# MAXIM-ADC2.net
KiCad netlist of a schematic drawn in Altium Designer
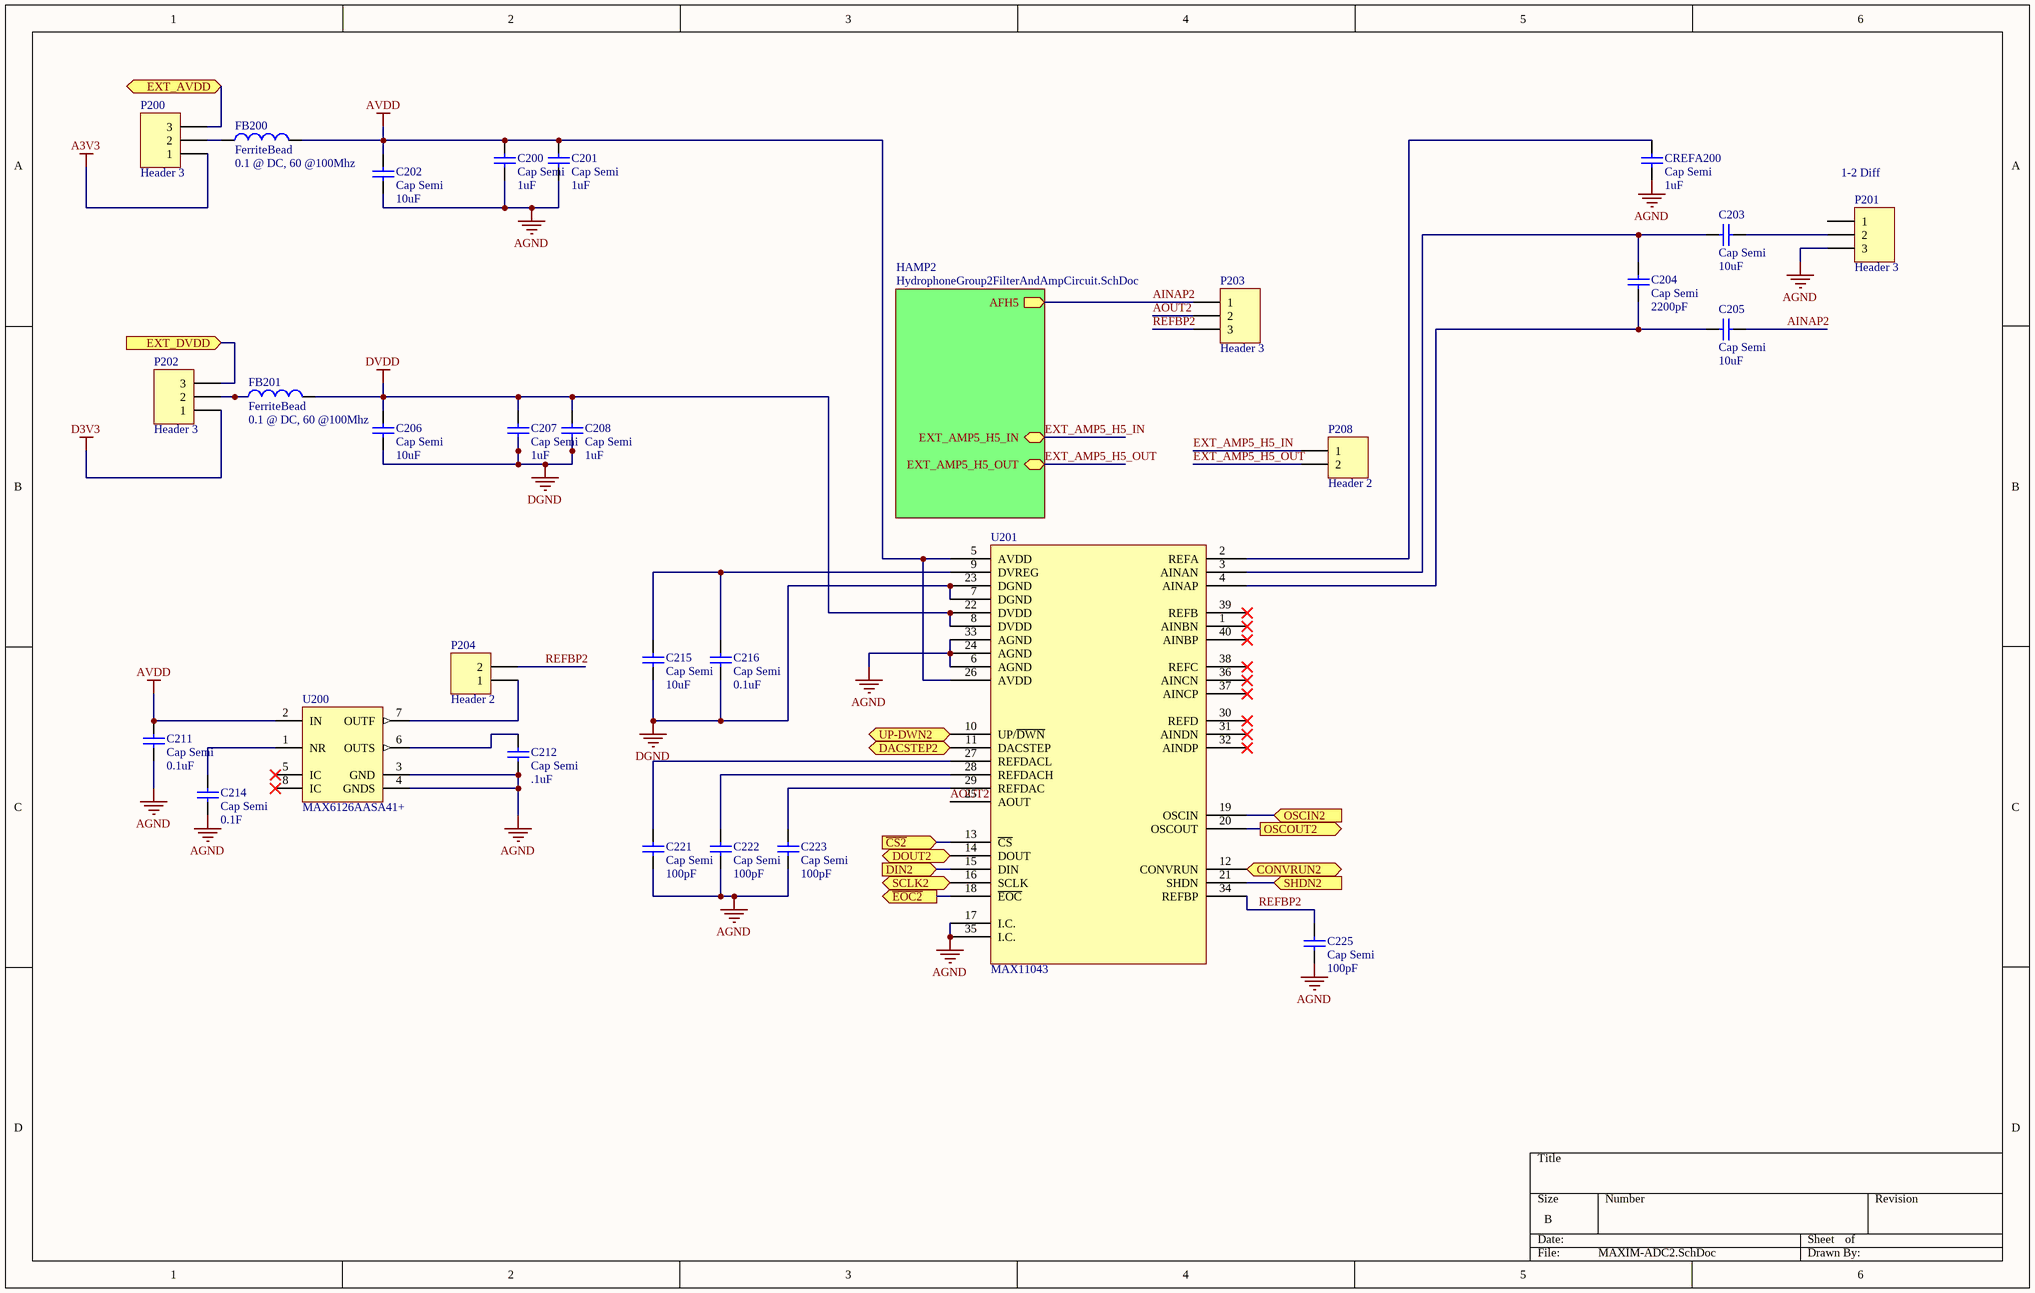
[diagram p0: MAXIM-ADC2.SchDoc]

(export (version "E")
  (design (tool "Eeschema 10.0.6"))
  (components
    (comp (ref "C200")
      (value "Cap Semi")
      (footprint "1608[0603]")
      (description "Capacitor (Semiconductor SIM Model)")
      (fields (field (name "ALTIUM_VALUE") "1uF") (field (name "PUBLISHER") "Altium Limited"))
      (libsource (lib "Miscellaneous Devices") (part "Cap Semi"))
    )
    (comp (ref "C201")
      (value "Cap Semi")
      (footprint "1608[0603]")
      (description "Capacitor (Semiconductor SIM Model)")
      (fields (field (name "ALTIUM_VALUE") "1uF") (field (name "PUBLISHER") "Altium Limited"))
      (libsource (lib "Miscellaneous Devices") (part "Cap Semi"))
    )
    (comp (ref "C202")
      (value "Cap Semi")
      (footprint "1608[0603]")
      (description "Capacitor (Semiconductor SIM Model)")
      (fields (field (name "ALTIUM_VALUE") "10uF") (field (name "PUBLISHER") "Altium Limited"))
      (libsource (lib "Miscellaneous Devices") (part "Cap Semi"))
    )
    (comp (ref "C203")
      (value "Cap Semi")
      (footprint "1608[0603]")
      (description "Capacitor (Semiconductor SIM Model)")
      (fields (field (name "ALTIUM_VALUE") "10uF") (field (name "PUBLISHER") "Altium Limited"))
      (libsource (lib "Miscellaneous Devices") (part "Cap Semi"))
    )
    (comp (ref "C204")
      (value "Cap Semi")
      (footprint "1608[0603]")
      (description "Capacitor (Semiconductor SIM Model)")
      (fields (field (name "ALTIUM_VALUE") "2200pF") (field (name "PUBLISHER") "Altium Limited"))
      (libsource (lib "Miscellaneous Devices") (part "Cap Semi"))
    )
    (comp (ref "C205")
      (value "Cap Semi")
      (footprint "1608[0603]")
      (description "Capacitor (Semiconductor SIM Model)")
      (fields (field (name "ALTIUM_VALUE") "10uF") (field (name "PUBLISHER") "Altium Limited"))
      (libsource (lib "Miscellaneous Devices") (part "Cap Semi"))
    )
    (comp (ref "C206")
      (value "Cap Semi")
      (footprint "1608[0603]")
      (description "Capacitor (Semiconductor SIM Model)")
      (fields (field (name "ALTIUM_VALUE") "10uF") (field (name "PUBLISHER") "Altium Limited"))
      (libsource (lib "Miscellaneous Devices") (part "Cap Semi"))
    )
    (comp (ref "C207")
      (value "Cap Semi")
      (footprint "1608[0603]")
      (description "Capacitor (Semiconductor SIM Model)")
      (fields (field (name "ALTIUM_VALUE") "1uF") (field (name "PUBLISHER") "Altium Limited"))
      (libsource (lib "Miscellaneous Devices") (part "Cap Semi"))
    )
    (comp (ref "C208")
      (value "Cap Semi")
      (footprint "1608[0603]")
      (description "Capacitor (Semiconductor SIM Model)")
      (fields (field (name "ALTIUM_VALUE") "1uF") (field (name "PUBLISHER") "Altium Limited"))
      (libsource (lib "Miscellaneous Devices") (part "Cap Semi"))
    )
    (comp (ref "C211")
      (value "Cap Semi")
      (footprint "1608[0603]")
      (description "Capacitor (Semiconductor SIM Model)")
      (fields (field (name "ALTIUM_VALUE") "0.1uF") (field (name "PUBLISHER") "Altium Limited"))
      (libsource (lib "Miscellaneous Devices") (part "Cap Semi"))
    )
    (comp (ref "C212")
      (value "Cap Semi")
      (footprint "1608[0603]")
      (description "Capacitor (Semiconductor SIM Model)")
      (fields (field (name "ALTIUM_VALUE") ".1uF") (field (name "PUBLISHER") "Altium Limited"))
      (libsource (lib "Miscellaneous Devices") (part "Cap Semi"))
    )
    (comp (ref "C214")
      (value "Cap Semi")
      (footprint "1608[0603]")
      (description "Capacitor (Semiconductor SIM Model)")
      (fields (field (name "ALTIUM_VALUE") "0.1F") (field (name "PUBLISHER") "Altium Limited"))
      (libsource (lib "Miscellaneous Devices") (part "Cap Semi"))
    )
    (comp (ref "C215")
      (value "Cap Semi")
      (footprint "1608[0603]")
      (description "Capacitor (Semiconductor SIM Model)")
      (fields (field (name "ALTIUM_VALUE") "10uF") (field (name "PUBLISHER") "Altium Limited"))
      (libsource (lib "Miscellaneous Devices") (part "Cap Semi"))
    )
    (comp (ref "C216")
      (value "Cap Semi")
      (footprint "1608[0603]")
      (description "Capacitor (Semiconductor SIM Model)")
      (fields (field (name "ALTIUM_VALUE") "0.1uF") (field (name "PUBLISHER") "Altium Limited"))
      (libsource (lib "Miscellaneous Devices") (part "Cap Semi"))
    )
    (comp (ref "C221")
      (value "Cap Semi")
      (footprint "1608[0603]")
      (description "Capacitor (Semiconductor SIM Model)")
      (fields (field (name "ALTIUM_VALUE") "100pF") (field (name "PUBLISHER") "Altium Limited"))
      (libsource (lib "Miscellaneous Devices") (part "Cap Semi"))
    )
    (comp (ref "C222")
      (value "Cap Semi")
      (footprint "1608[0603]")
      (description "Capacitor (Semiconductor SIM Model)")
      (fields (field (name "ALTIUM_VALUE") "100pF") (field (name "PUBLISHER") "Altium Limited"))
      (libsource (lib "Miscellaneous Devices") (part "Cap Semi"))
    )
    (comp (ref "C223")
      (value "Cap Semi")
      (footprint "1608[0603]")
      (description "Capacitor (Semiconductor SIM Model)")
      (fields (field (name "ALTIUM_VALUE") "100pF") (field (name "PUBLISHER") "Altium Limited"))
      (libsource (lib "Miscellaneous Devices") (part "Cap Semi"))
    )
    (comp (ref "C225")
      (value "Cap Semi")
      (footprint "1608[0603]")
      (description "Capacitor (Semiconductor SIM Model)")
      (fields (field (name "ALTIUM_VALUE") "100pF") (field (name "PUBLISHER") "Altium Limited"))
      (libsource (lib "Miscellaneous Devices") (part "Cap Semi"))
    )
    (comp (ref "CREFA200")
      (value "Cap Semi")
      (footprint "1608[0603]")
      (description "Capacitor (Semiconductor SIM Model)")
      (fields (field (name "ALTIUM_VALUE") "1uF") (field (name "PUBLISHER") "Altium Limited"))
      (libsource (lib "Miscellaneous Devices") (part "Cap Semi"))
    )
    (comp (ref "FB200")
      (value "FerriteBead")
      (footprint "0603")
      (description "Inductor")
      (fields
        (field (name "ALTIUM_VALUE") "0.1 @ DC, 60 @100Mhz")
        (field (name "PUBLISHER") "Altium Limited")
      )
      (libsource (lib "Miscellaneous Devices") (part "Inductor"))
    )
    (comp (ref "FB201")
      (value "FerriteBead")
      (footprint "0603")
      (description "Inductor")
      (fields
        (field (name "ALTIUM_VALUE") "0.1 @ DC, 60 @100Mhz")
        (field (name "PUBLISHER") "Altium Limited")
      )
      (libsource (lib "Miscellaneous Devices") (part "Inductor"))
    )
    (comp (ref "P200")
      (value "Header 3")
      (footprint "HDR1X3")
      (description "Header, 3-Pin")
      (fields (field (name "PUBLISHER") "Altium Limited"))
      (libsource (lib "Miscellaneous Connectors") (part "Header 3"))
    )
    (comp (ref "P201")
      (value "Header 3")
      (footprint "HDR1X3")
      (description "Header, 3-Pin")
      (fields (field (name "PUBLISHER") "Altium Limited"))
      (libsource (lib "") (part "Header 3_1"))
    )
    (comp (ref "P202")
      (value "Header 3")
      (footprint "HDR1X3")
      (description "Header, 3-Pin")
      (fields (field (name "PUBLISHER") "Altium Limited"))
      (libsource (lib "Miscellaneous Connectors") (part "Header 3"))
    )
    (comp (ref "P203")
      (value "Header 3")
      (footprint "HDR1X3")
      (description "Header, 3-Pin")
      (fields (field (name "PUBLISHER") "Altium Limited"))
      (libsource (lib "") (part "Header 3_1"))
    )
    (comp (ref "P204")
      (value "Header 2")
      (footprint "HDR1X2")
      (description "Header, 2-Pin")
      (fields (field (name "PUBLISHER") "Altium Limited"))
      (libsource (lib "") (part "Header 2_1"))
    )
    (comp (ref "P208")
      (value "Header 2")
      (footprint "HDR1X2")
      (description "Header, 2-Pin")
      (fields (field (name "PUBLISHER") "Altium Limited"))
      (libsource (lib "Miscellaneous Connectors") (part "Header 2"))
    )
    (comp (ref "U200")
      (value "MAX6126AASA41+")
      (footprint "MAXM-S8+4_M")
      (fields (field (name "MANUFACTURER") "Maxim"))
      (libsource (lib "altium-import") (part "root_0_CMP-0977-00016-1_"))
    )
    (comp (ref "U201")
      (value "MAX11043")
      (footprint "QFN50P600X600X80_HS-41N")
      (libsource (lib "Max11043") (part "MAX11043"))
    )
  )
  (nets
    (net (code "1") (name "/AINAP2") (class "Default")
      (node (ref "C205") (pin "1") (pinfunction "1_1") (pintype "passive"))
      (node (ref "P203") (pin "1") (pinfunction "1_1") (pintype "passive"))
    )
    (net (code "2") (name "/AOUT2") (class "Default")
      (node (ref "P203") (pin "2") (pinfunction "2_2") (pintype "passive"))
      (node (ref "U201") (pin "25") (pinfunction "AOUT_25") (pintype "passive"))
    )
    (net (code "3") (name "/CONVRUN2") (class "Default")
      (node (ref "U201") (pin "12") (pinfunction "CONVRUN_12") (pintype "passive"))
    )
    (net (code "4") (name "/DACSTEP2") (class "Default")
      (node (ref "U201") (pin "11") (pinfunction "DACSTEP_11") (pintype "passive"))
    )
    (net (code "5") (name "/DIN2") (class "Default")
      (node (ref "U201") (pin "15") (pinfunction "DIN_15") (pintype "passive"))
    )
    (net (code "6") (name "/DOUT2") (class "Default")
      (node (ref "U201") (pin "14") (pinfunction "DOUT_14") (pintype "passive"))
    )
    (net (code "7") (name "/EXT_AMP5_H5_IN") (class "Default")
      (node (ref "P208") (pin "1") (pinfunction "1_1") (pintype "passive"))
    )
    (net (code "8") (name "/EXT_AMP5_H5_OUT") (class "Default")
      (node (ref "P208") (pin "2") (pinfunction "2_2") (pintype "passive"))
    )
    (net (code "9") (name "/EXT_AVDD") (class "Default")
      (node (ref "P200") (pin "3") (pinfunction "3_3") (pintype "passive"))
    )
    (net (code "10") (name "/EXT_DVDD") (class "Default")
      (node (ref "P202") (pin "3") (pinfunction "3_3") (pintype "passive"))
    )
    (net (code "11") (name "/OSCIN2") (class "Default")
      (node (ref "U201") (pin "19") (pinfunction "OSCIN_19") (pintype "passive"))
    )
    (net (code "12") (name "/OSCOUT2") (class "Default")
      (node (ref "U201") (pin "20") (pinfunction "OSCOUT_20") (pintype "passive"))
    )
    (net (code "13") (name "/REFBP2") (class "Default")
      (node (ref "C225") (pin "1") (pinfunction "1_1") (pintype "passive"))
      (node (ref "P203") (pin "3") (pinfunction "3_3") (pintype "passive"))
      (node (ref "P204") (pin "2") (pinfunction "2_2") (pintype "passive"))
      (node (ref "U201") (pin "34") (pinfunction "REFBP_34") (pintype "passive"))
    )
    (net (code "14") (name "/SCLK2") (class "Default")
      (node (ref "U201") (pin "16") (pinfunction "SCLK_16") (pintype "passive"))
    )
    (net (code "15") (name "/SHDN2") (class "Default")
      (node (ref "U201") (pin "21") (pinfunction "SHDN_21") (pintype "passive"))
    )
    (net (code "16") (name "/UP-DWN2") (class "Default")
      (node (ref "U201") (pin "10") (pinfunction "UP/~{DWN}_10") (pintype "passive"))
    )
    (net (code "17") (name "/~{CS2}") (class "Default")
      (node (ref "U201") (pin "13") (pinfunction "~{CS}_13") (pintype "passive"))
    )
    (net (code "18") (name "/~{EOC2}") (class "Default")
      (node (ref "U201") (pin "18") (pinfunction "~{EOC}_18") (pintype "passive"))
    )
    (net (code "19") (name "A3V3") (class "Default")
      (node (ref "P200") (pin "1") (pinfunction "1_1") (pintype "passive"))
    )
    (net (code "20") (name "AGND") (class "Default")
      (node (ref "C200") (pin "2") (pinfunction "2_2") (pintype "passive"))
      (node (ref "C201") (pin "2") (pinfunction "2_2") (pintype "passive"))
      (node (ref "C202") (pin "2") (pinfunction "2_2") (pintype "passive"))
      (node (ref "C211") (pin "2") (pinfunction "2_2") (pintype "passive"))
      (node (ref "C212") (pin "2") (pinfunction "2_2") (pintype "passive"))
      (node (ref "C214") (pin "2") (pinfunction "2_2") (pintype "passive"))
      (node (ref "C221") (pin "1") (pinfunction "1_1") (pintype "passive"))
      (node (ref "C222") (pin "2") (pinfunction "2_2") (pintype "passive"))
      (node (ref "C223") (pin "1") (pinfunction "1_1") (pintype "passive"))
      (node (ref "C225") (pin "2") (pinfunction "2_2") (pintype "passive"))
      (node (ref "CREFA200") (pin "1") (pinfunction "1_1") (pintype "passive"))
      (node (ref "P201") (pin "3") (pinfunction "3_3") (pintype "passive"))
      (node (ref "U200") (pin "3") (pinfunction "GND_3") (pintype "power_in"))
      (node (ref "U200") (pin "4") (pinfunction "GNDS_4") (pintype "power_in"))
      (node (ref "U201") (pin "17") (pinfunction "I.C._17") (pintype "passive"))
      (node (ref "U201") (pin "24") (pinfunction "AGND_24") (pintype "passive"))
      (node (ref "U201") (pin "33") (pinfunction "AGND_33") (pintype "passive"))
      (node (ref "U201") (pin "35") (pinfunction "I.C._35") (pintype "passive"))
      (node (ref "U201") (pin "6") (pinfunction "AGND_6") (pintype "passive"))
    )
    (net (code "21") (name "AVDD") (class "Default")
      (node (ref "C200") (pin "1") (pinfunction "1_1") (pintype "passive"))
      (node (ref "C201") (pin "1") (pinfunction "1_1") (pintype "passive"))
      (node (ref "C202") (pin "1") (pinfunction "1_1") (pintype "passive"))
      (node (ref "C211") (pin "1") (pinfunction "1_1") (pintype "passive"))
      (node (ref "FB200") (pin "2") (pinfunction "2_2") (pintype "passive"))
      (node (ref "U200") (pin "2") (pinfunction "IN_2") (pintype "power_in"))
      (node (ref "U201") (pin "26") (pinfunction "AVDD_26") (pintype "passive"))
      (node (ref "U201") (pin "5") (pinfunction "AVDD_5") (pintype "passive"))
    )
    (net (code "22") (name "D3V3") (class "Default")
      (node (ref "P202") (pin "1") (pinfunction "1_1") (pintype "passive"))
    )
    (net (code "23") (name "DGND") (class "Default")
      (node (ref "C206") (pin "2") (pinfunction "2_2") (pintype "passive"))
      (node (ref "C207") (pin "2") (pinfunction "2_2") (pintype "passive"))
      (node (ref "C208") (pin "2") (pinfunction "2_2") (pintype "passive"))
      (node (ref "C215") (pin "2") (pinfunction "2_2") (pintype "passive"))
      (node (ref "C216") (pin "2") (pinfunction "2_2") (pintype "passive"))
      (node (ref "U201") (pin "23") (pinfunction "DGND_23") (pintype "passive"))
      (node (ref "U201") (pin "7") (pinfunction "DGND_7") (pintype "passive"))
    )
    (net (code "24") (name "DVDD") (class "Default")
      (node (ref "C206") (pin "1") (pinfunction "1_1") (pintype "passive"))
      (node (ref "C207") (pin "1") (pinfunction "1_1") (pintype "passive"))
      (node (ref "C208") (pin "1") (pinfunction "1_1") (pintype "passive"))
      (node (ref "FB201") (pin "2") (pinfunction "2_2") (pintype "passive"))
      (node (ref "U201") (pin "22") (pinfunction "DVDD_22") (pintype "passive"))
      (node (ref "U201") (pin "8") (pinfunction "DVDD_8") (pintype "passive"))
    )
    (net (code "25") (name "Net-(C203-Pad1)") (class "Default")
      (node (ref "C203") (pin "1") (pinfunction "1_1") (pintype "passive"))
      (node (ref "P201") (pin "2") (pinfunction "2_2") (pintype "passive"))
    )
    (net (code "26") (name "Net-(FB200-Pad1)") (class "Default")
      (node (ref "FB200") (pin "1") (pinfunction "1_1") (pintype "passive"))
      (node (ref "P200") (pin "2") (pinfunction "2_2") (pintype "passive"))
    )
    (net (code "27") (name "Net-(FB201-Pad1)") (class "Default")
      (node (ref "FB201") (pin "1") (pinfunction "1_1") (pintype "passive"))
      (node (ref "P202") (pin "2") (pinfunction "2_2") (pintype "passive"))
    )
    (net (code "28") (name "Net-(U200-NR)") (class "Default")
      (node (ref "C214") (pin "1") (pinfunction "1_1") (pintype "passive"))
      (node (ref "U200") (pin "1") (pinfunction "NR_1") (pintype "passive"))
    )
    (net (code "29") (name "Net-(U200-OUTF)") (class "Default")
      (node (ref "P204") (pin "1") (pinfunction "1_1") (pintype "passive"))
      (node (ref "U200") (pin "7") (pinfunction "OUTF_7") (pintype "output"))
    )
    (net (code "30") (name "Net-(U200-OUTS)") (class "Default")
      (node (ref "C212") (pin "1") (pinfunction "1_1") (pintype "passive"))
      (node (ref "U200") (pin "6") (pinfunction "OUTS_6") (pintype "output"))
    )
    (net (code "31") (name "Net-(U201-AINAN)") (class "Default")
      (node (ref "C203") (pin "2") (pinfunction "2_2") (pintype "passive"))
      (node (ref "C204") (pin "2") (pinfunction "2_2") (pintype "passive"))
      (node (ref "U201") (pin "3") (pinfunction "AINAN_3") (pintype "passive"))
    )
    (net (code "32") (name "Net-(U201-AINAP)") (class "Default")
      (node (ref "C204") (pin "1") (pinfunction "1_1") (pintype "passive"))
      (node (ref "C205") (pin "2") (pinfunction "2_2") (pintype "passive"))
      (node (ref "U201") (pin "4") (pinfunction "AINAP_4") (pintype "passive"))
    )
    (net (code "33") (name "Net-(U201-DVREG)") (class "Default")
      (node (ref "C215") (pin "1") (pinfunction "1_1") (pintype "passive"))
      (node (ref "C216") (pin "1") (pinfunction "1_1") (pintype "passive"))
      (node (ref "U201") (pin "9") (pinfunction "DVREG_9") (pintype "passive"))
    )
    (net (code "34") (name "Net-(U201-REFA)") (class "Default")
      (node (ref "CREFA200") (pin "2") (pinfunction "2_2") (pintype "passive"))
      (node (ref "U201") (pin "2") (pinfunction "REFA_2") (pintype "passive"))
    )
    (net (code "35") (name "Net-(U201-REFDAC)") (class "Default")
      (node (ref "C223") (pin "2") (pinfunction "2_2") (pintype "passive"))
      (node (ref "U201") (pin "29") (pinfunction "REFDAC_29") (pintype "passive"))
    )
    (net (code "36") (name "Net-(U201-REFDACH)") (class "Default")
      (node (ref "C222") (pin "1") (pinfunction "1_1") (pintype "passive"))
      (node (ref "U201") (pin "28") (pinfunction "REFDACH_28") (pintype "passive"))
    )
    (net (code "37") (name "Net-(U201-REFDACL)") (class "Default")
      (node (ref "C221") (pin "2") (pinfunction "2_2") (pintype "passive"))
      (node (ref "U201") (pin "27") (pinfunction "REFDACL_27") (pintype "passive"))
    )
    (net (code "38") (name "unconnected-(P201-Pad1)") (class "Default")
      (node (ref "P201") (pin "1") (pinfunction "1_1") (pintype "passive"))
    )
    (net (code "39") (name "unconnected-(U200-IC-Pad5)") (class "Default")
      (node (ref "U200") (pin "5") (pinfunction "IC_5") (pintype "passive+no_connect"))
    )
    (net (code "40") (name "unconnected-(U200-IC-Pad8)") (class "Default")
      (node (ref "U200") (pin "8") (pinfunction "IC_8") (pintype "passive+no_connect"))
    )
    (net (code "41") (name "unconnected-(U201-AINBN-Pad1)") (class "Default")
      (node (ref "U201") (pin "1") (pinfunction "AINBN_1") (pintype "passive+no_connect"))
    )
    (net (code "42") (name "unconnected-(U201-AINBP-Pad40)") (class "Default")
      (node (ref "U201") (pin "40") (pinfunction "AINBP_40") (pintype "passive+no_connect"))
    )
    (net (code "43") (name "unconnected-(U201-AINCN-Pad36)") (class "Default")
      (node (ref "U201") (pin "36") (pinfunction "AINCN_36") (pintype "passive+no_connect"))
    )
    (net (code "44") (name "unconnected-(U201-AINCP-Pad37)") (class "Default")
      (node (ref "U201") (pin "37") (pinfunction "AINCP_37") (pintype "passive+no_connect"))
    )
    (net (code "45") (name "unconnected-(U201-AINDN-Pad31)") (class "Default")
      (node (ref "U201") (pin "31") (pinfunction "AINDN_31") (pintype "passive+no_connect"))
    )
    (net (code "46") (name "unconnected-(U201-AINDP-Pad32)") (class "Default")
      (node (ref "U201") (pin "32") (pinfunction "AINDP_32") (pintype "passive+no_connect"))
    )
    (net (code "47") (name "unconnected-(U201-REFB-Pad39)") (class "Default")
      (node (ref "U201") (pin "39") (pinfunction "REFB_39") (pintype "passive+no_connect"))
    )
    (net (code "48") (name "unconnected-(U201-REFC-Pad38)") (class "Default")
      (node (ref "U201") (pin "38") (pinfunction "REFC_38") (pintype "passive+no_connect"))
    )
    (net (code "49") (name "unconnected-(U201-REFD-Pad30)") (class "Default")
      (node (ref "U201") (pin "30") (pinfunction "REFD_30") (pintype "passive+no_connect"))
    )
  )
)
